# Test_Points_Sheet.net
KiCad netlist of a schematic drawn in Altium Designer
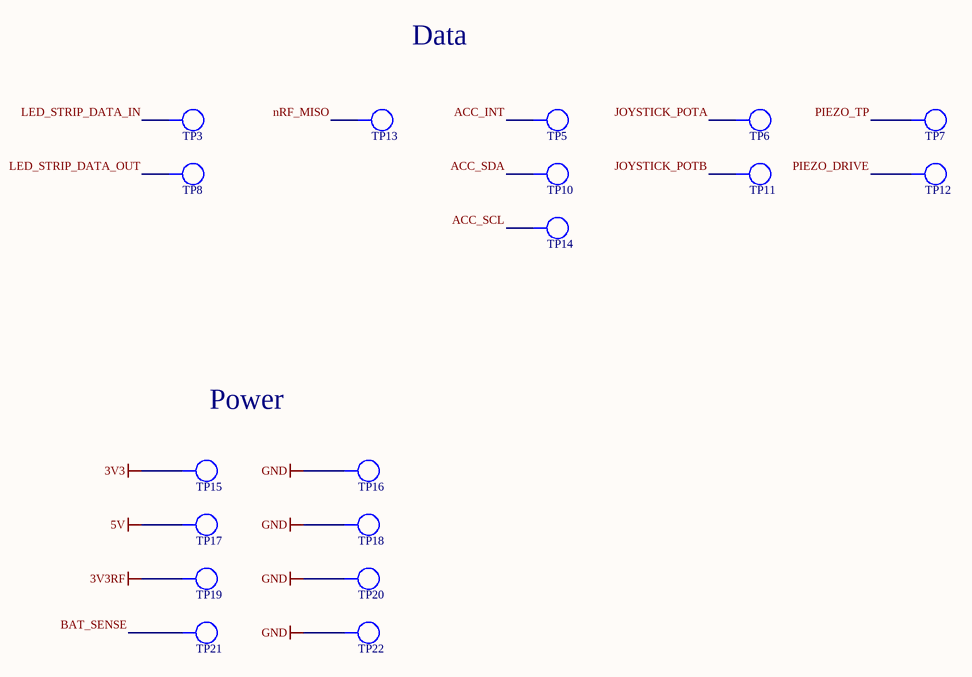
[diagram p0: Test Points Sheet.SchDoc]

(export (version "E")
  (design (tool "Eeschema 10.0.6"))
  (components
    (comp (ref "TP3")
      (value "TP")
      (footprint "TP_1206")
      (description "Test-Point 3.3x1.6x2.1mm SMD")
      (fields
        (field (name "MANUFACTURER") "Harwin Inc")
        (field (name "MANUFACTURER PART NUMBER") "S1751-46R")
      )
      (libsource (lib "ECE AD19Components_19V1") (part "TP_1206"))
    )
    (comp (ref "TP5")
      (value "TP")
      (footprint "TP_1206")
      (description "Test-Point 3.3x1.6x2.1mm SMD")
      (fields
        (field (name "MANUFACTURER") "Harwin Inc")
        (field (name "MANUFACTURER PART NUMBER") "S1751-46R")
      )
      (libsource (lib "ECE AD19Components_19V1") (part "TP_1206"))
    )
    (comp (ref "TP6")
      (value "TP")
      (footprint "TP_1206")
      (description "Test-Point 3.3x1.6x2.1mm SMD")
      (fields
        (field (name "MANUFACTURER") "Harwin Inc")
        (field (name "MANUFACTURER PART NUMBER") "S1751-46R")
      )
      (libsource (lib "ECE AD19Components_19V1") (part "TP_1206"))
    )
    (comp (ref "TP7")
      (value "TP")
      (footprint "TP_1206")
      (description "Test-Point 3.3x1.6x2.1mm SMD")
      (fields
        (field (name "MANUFACTURER") "Harwin Inc")
        (field (name "MANUFACTURER PART NUMBER") "S1751-46R")
      )
      (libsource (lib "ECE AD19Components_19V1") (part "TP_1206"))
    )
    (comp (ref "TP8")
      (value "TP")
      (footprint "TP_1206")
      (description "Test-Point 3.3x1.6x2.1mm SMD")
      (fields
        (field (name "MANUFACTURER") "Harwin Inc")
        (field (name "MANUFACTURER PART NUMBER") "S1751-46R")
      )
      (libsource (lib "ECE AD19Components_19V1") (part "TP_1206"))
    )
    (comp (ref "TP10")
      (value "TP")
      (footprint "TP_1206")
      (description "Test-Point 3.3x1.6x2.1mm SMD")
      (fields
        (field (name "MANUFACTURER") "Harwin Inc")
        (field (name "MANUFACTURER PART NUMBER") "S1751-46R")
      )
      (libsource (lib "ECE AD19Components_19V1") (part "TP_1206"))
    )
    (comp (ref "TP11")
      (value "TP")
      (footprint "TP_1206")
      (description "Test-Point 3.3x1.6x2.1mm SMD")
      (fields
        (field (name "MANUFACTURER") "Harwin Inc")
        (field (name "MANUFACTURER PART NUMBER") "S1751-46R")
      )
      (libsource (lib "ECE AD19Components_19V1") (part "TP_1206"))
    )
    (comp (ref "TP12")
      (value "TP")
      (footprint "TP_1206")
      (description "Test-Point 3.3x1.6x2.1mm SMD")
      (fields
        (field (name "MANUFACTURER") "Harwin Inc")
        (field (name "MANUFACTURER PART NUMBER") "S1751-46R")
      )
      (libsource (lib "ECE AD19Components_19V1") (part "TP_1206"))
    )
    (comp (ref "TP13")
      (value "TP")
      (footprint "TP_1206")
      (description "Test-Point 3.3x1.6x2.1mm SMD")
      (fields
        (field (name "MANUFACTURER") "Harwin Inc")
        (field (name "MANUFACTURER PART NUMBER") "S1751-46R")
      )
      (libsource (lib "ECE AD19Components_19V1") (part "TP_1206"))
    )
    (comp (ref "TP14")
      (value "TP")
      (footprint "TP_1206")
      (description "Test-Point 3.3x1.6x2.1mm SMD")
      (fields
        (field (name "MANUFACTURER") "Harwin Inc")
        (field (name "MANUFACTURER PART NUMBER") "S1751-46R")
      )
      (libsource (lib "ECE AD19Components_19V1") (part "TP_1206"))
    )
    (comp (ref "TP15")
      (value "TP")
      (footprint "TP_1206")
      (description "Test-Point 3.3x1.6x2.1mm SMD")
      (fields
        (field (name "MANUFACTURER") "Harwin Inc")
        (field (name "MANUFACTURER PART NUMBER") "S1751-46R")
      )
      (libsource (lib "ECE AD19Components_19V1") (part "TP_1206"))
    )
    (comp (ref "TP16")
      (value "TP")
      (footprint "TP_1206")
      (description "Test-Point 3.3x1.6x2.1mm SMD")
      (fields
        (field (name "MANUFACTURER") "Harwin Inc")
        (field (name "MANUFACTURER PART NUMBER") "S1751-46R")
      )
      (libsource (lib "ECE AD19Components_19V1") (part "TP_1206"))
    )
    (comp (ref "TP17")
      (value "TP")
      (footprint "TP_1206")
      (description "Test-Point 3.3x1.6x2.1mm SMD")
      (fields
        (field (name "MANUFACTURER") "Harwin Inc")
        (field (name "MANUFACTURER PART NUMBER") "S1751-46R")
      )
      (libsource (lib "ECE AD19Components_19V1") (part "TP_1206"))
    )
    (comp (ref "TP18")
      (value "TP")
      (footprint "TP_1206")
      (description "Test-Point 3.3x1.6x2.1mm SMD")
      (fields
        (field (name "MANUFACTURER") "Harwin Inc")
        (field (name "MANUFACTURER PART NUMBER") "S1751-46R")
      )
      (libsource (lib "ECE AD19Components_19V1") (part "TP_1206"))
    )
    (comp (ref "TP19")
      (value "TP")
      (footprint "TP_1206")
      (description "Test-Point 3.3x1.6x2.1mm SMD")
      (fields
        (field (name "MANUFACTURER") "Harwin Inc")
        (field (name "MANUFACTURER PART NUMBER") "S1751-46R")
      )
      (libsource (lib "ECE AD19Components_19V1") (part "TP_1206"))
    )
    (comp (ref "TP20")
      (value "TP")
      (footprint "TP_1206")
      (description "Test-Point 3.3x1.6x2.1mm SMD")
      (fields
        (field (name "MANUFACTURER") "Harwin Inc")
        (field (name "MANUFACTURER PART NUMBER") "S1751-46R")
      )
      (libsource (lib "ECE AD19Components_19V1") (part "TP_1206"))
    )
    (comp (ref "TP21")
      (value "TP")
      (footprint "TP_1206")
      (description "Test-Point 3.3x1.6x2.1mm SMD")
      (fields
        (field (name "MANUFACTURER") "Harwin Inc")
        (field (name "MANUFACTURER PART NUMBER") "S1751-46R")
      )
      (libsource (lib "ECE AD19Components_19V1") (part "TP_1206"))
    )
    (comp (ref "TP22")
      (value "TP")
      (footprint "TP_1206")
      (description "Test-Point 3.3x1.6x2.1mm SMD")
      (fields
        (field (name "MANUFACTURER") "Harwin Inc")
        (field (name "MANUFACTURER PART NUMBER") "S1751-46R")
      )
      (libsource (lib "ECE AD19Components_19V1") (part "TP_1206"))
    )
  )
  (nets
    (net (code "1") (name "/ACC_INT") (class "Default")
      (node (ref "TP5") (pin "1") (pinfunction "1_1") (pintype "passive"))
    )
    (net (code "2") (name "/ACC_SCL") (class "Default")
      (node (ref "TP14") (pin "1") (pinfunction "1_1") (pintype "passive"))
    )
    (net (code "3") (name "/ACC_SDA") (class "Default")
      (node (ref "TP10") (pin "1") (pinfunction "1_1") (pintype "passive"))
    )
    (net (code "4") (name "/BAT_SENSE") (class "Default")
      (node (ref "TP21") (pin "1") (pinfunction "1_1") (pintype "passive"))
    )
    (net (code "5") (name "/JOYSTICK_POTA") (class "Default")
      (node (ref "TP6") (pin "1") (pinfunction "1_1") (pintype "passive"))
    )
    (net (code "6") (name "/JOYSTICK_POTB") (class "Default")
      (node (ref "TP11") (pin "1") (pinfunction "1_1") (pintype "passive"))
    )
    (net (code "7") (name "/LED_STRIP_DATA_IN") (class "Default")
      (node (ref "TP3") (pin "1") (pinfunction "1_1") (pintype "passive"))
    )
    (net (code "8") (name "/LED_STRIP_DATA_OUT") (class "Default")
      (node (ref "TP8") (pin "1") (pinfunction "1_1") (pintype "passive"))
    )
    (net (code "9") (name "/PIEZO_DRIVE") (class "Default")
      (node (ref "TP12") (pin "1") (pinfunction "1_1") (pintype "passive"))
    )
    (net (code "10") (name "/PIEZO_TP") (class "Default")
      (node (ref "TP7") (pin "1") (pinfunction "1_1") (pintype "passive"))
    )
    (net (code "11") (name "/nRF_MISO") (class "Default")
      (node (ref "TP13") (pin "1") (pinfunction "1_1") (pintype "passive"))
    )
    (net (code "12") (name "3V3") (class "Default")
      (node (ref "TP15") (pin "1") (pinfunction "1_1") (pintype "passive"))
    )
    (net (code "13") (name "3V3RF") (class "Default")
      (node (ref "TP19") (pin "1") (pinfunction "1_1") (pintype "passive"))
    )
    (net (code "14") (name "5V") (class "Default")
      (node (ref "TP17") (pin "1") (pinfunction "1_1") (pintype "passive"))
    )
    (net (code "15") (name "GND") (class "Default")
      (node (ref "TP16") (pin "1") (pinfunction "1_1") (pintype "passive"))
      (node (ref "TP18") (pin "1") (pinfunction "1_1") (pintype "passive"))
      (node (ref "TP20") (pin "1") (pinfunction "1_1") (pintype "passive"))
      (node (ref "TP22") (pin "1") (pinfunction "1_1") (pintype "passive"))
    )
  )
)
